# SUPPLY.net
KiCad netlist of a schematic drawn in Altium Designer
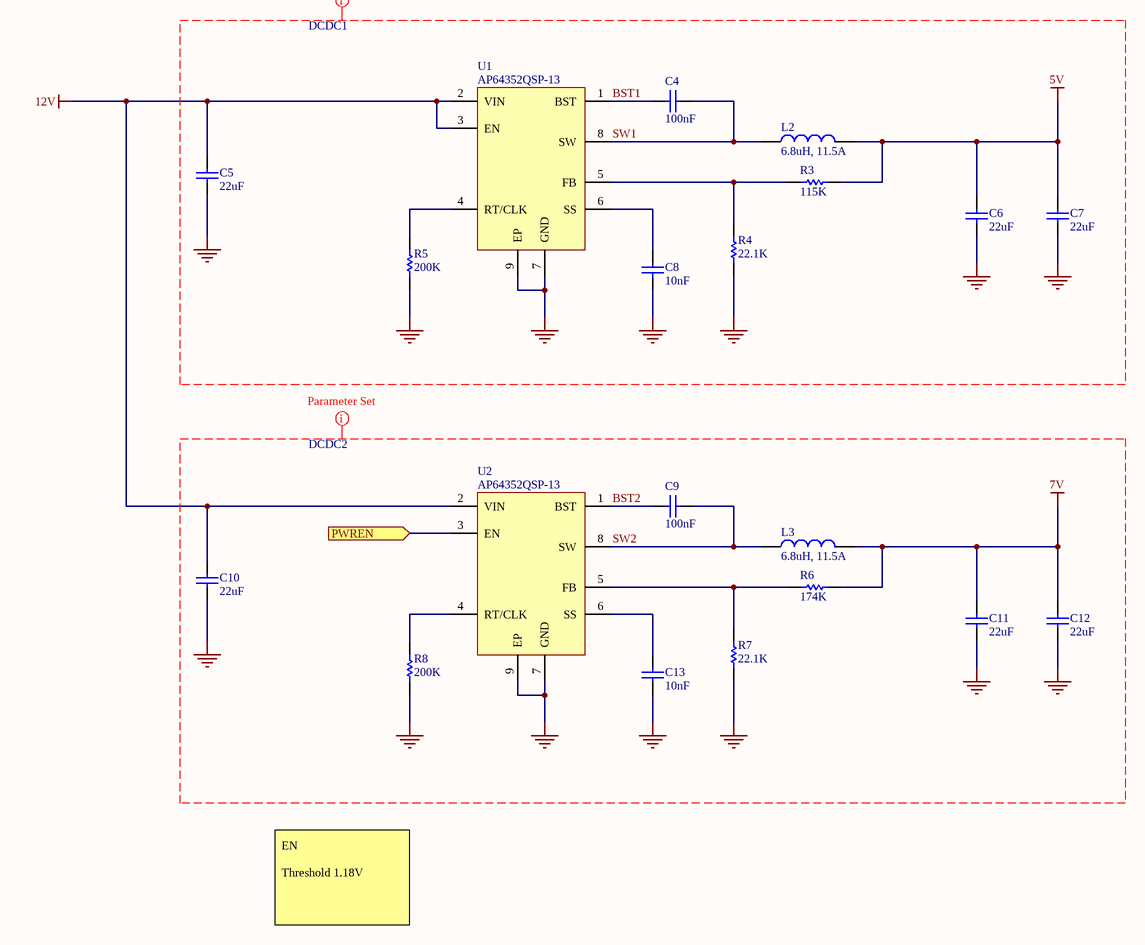
[diagram p0: SUPPLY.SchDoc]

(export (version "E")
  (design (tool "Eeschema 10.0.6"))
  (components
    (comp (ref "C4")
      (value "100nF")
      (footprint "CAP_0603_H090 (_IPC_MD)")
      (description "CAP CER 100NF 50V X7R 0603")
      (fields (field (name "PART NUMBER") "CL10B104KB8NNNC") (field (name "Comment") "100nF 0603"))
      (libsource (lib "MUAB_Altium_Lib") (part "CAP"))
    )
    (comp (ref "C5")
      (value "22uF")
      (footprint "CAP_1210_H090 (_IPC_HD)")
      (description "CAP CER 22UF 25V X7R 1210")
      (fields (field (name "PART NUMBER") "MA1210XR226K250ER") (field (name "Comment") "22uF 1210"))
      (libsource (lib "MUAB_Altium_Lib") (part "CAP"))
    )
    (comp (ref "C6")
      (value "22uF")
      (footprint "CAP_1210_H090 (_IPC_HD)")
      (description "CAP CER 22UF 25V X7R 1210")
      (fields (field (name "PART NUMBER") "MA1210XR226K250ER") (field (name "Comment") "22uF 1210"))
      (libsource (lib "MUAB_Altium_Lib") (part "CAP"))
    )
    (comp (ref "C7")
      (value "22uF")
      (footprint "CAP_1210_H090 (_IPC_HD)")
      (description "CAP CER 22UF 25V X7R 1210")
      (fields (field (name "PART NUMBER") "MA1210XR226K250ER") (field (name "Comment") "22uF 1210"))
      (libsource (lib "MUAB_Altium_Lib") (part "CAP"))
    )
    (comp (ref "C8")
      (value "10nF")
      (footprint "CAP_0603_H090 (_IPC_MD)")
      (description "CAP CER 10NF 50V C0G/NP0 0603")
      (fields (field (name "PART NUMBER") "CGA3E2C0G1H103J080AA") (field (name "Comment") "10nF 0603"))
      (libsource (lib "MUAB_Altium_Lib") (part "CAP"))
    )
    (comp (ref "C9")
      (value "100nF")
      (footprint "CAP_0603_H090 (_IPC_MD)")
      (description "CAP CER 100NF 50V X7R 0603")
      (fields (field (name "PART NUMBER") "CL10B104KB8NNNC") (field (name "Comment") "100nF 0603"))
      (libsource (lib "MUAB_Altium_Lib") (part "CAP"))
    )
    (comp (ref "C10")
      (value "22uF")
      (footprint "CAP_1210_H090 (_IPC_HD)")
      (description "CAP CER 22UF 25V X7R 1210")
      (fields (field (name "PART NUMBER") "MA1210XR226K250ER") (field (name "Comment") "22uF 1210"))
      (libsource (lib "MUAB_Altium_Lib") (part "CAP"))
    )
    (comp (ref "C11")
      (value "22uF")
      (footprint "CAP_1210_H090 (_IPC_HD)")
      (description "CAP CER 22UF 25V X7R 1210")
      (fields (field (name "PART NUMBER") "MA1210XR226K250ER") (field (name "Comment") "22uF 1210"))
      (libsource (lib "MUAB_Altium_Lib") (part "CAP"))
    )
    (comp (ref "C12")
      (value "22uF")
      (footprint "CAP_1210_H090 (_IPC_HD)")
      (description "CAP CER 22UF 25V X7R 1210")
      (fields (field (name "PART NUMBER") "MA1210XR226K250ER") (field (name "Comment") "22uF 1210"))
      (libsource (lib "MUAB_Altium_Lib") (part "CAP"))
    )
    (comp (ref "C13")
      (value "10nF")
      (footprint "CAP_0603_H090 (_IPC_MD)")
      (description "CAP CER 10NF 50V C0G/NP0 0603")
      (fields (field (name "PART NUMBER") "CGA3E2C0G1H103J080AA") (field (name "Comment") "10nF 0603"))
      (libsource (lib "MUAB_Altium_Lib") (part "CAP"))
    )
    (comp (ref "L2")
      (value "6.8uH, 11.5A")
      (footprint "WE-HCC_1090")
      (description "WE-HCC SMT High Current Cube Inductor, size 1090, 6.8uH, 11.5A")
      (fields
        (field (name "MANUFACTURER PART NUMBER") "7443330680")
        (field (name "MANUFACTURER") "Wurth Elektronik")
      )
      (libsource (lib "WE-HCC (rev21a)") (part "7443330680"))
    )
    (comp (ref "L3")
      (value "6.8uH, 11.5A")
      (footprint "WE-HCC_1090")
      (description "WE-HCC SMT High Current Cube Inductor, size 1090, 6.8uH, 11.5A")
      (fields
        (field (name "MANUFACTURER PART NUMBER") "7443330680")
        (field (name "MANUFACTURER") "Wurth Elektronik")
      )
      (libsource (lib "WE-HCC (rev21a)") (part "7443330680"))
    )
    (comp (ref "R3")
      (value "115K")
      (footprint "RES_0603_H050 (_IPC_MD)")
      (description "115K 1% 0,1W 75V 0603")
      (fields (field (name "PART NUMBER") "RES115K1%0603"))
      (libsource (lib "MUAB_Altium_Lib") (part "RES"))
    )
    (comp (ref "R4")
      (value "22.1K")
      (footprint "RES_0603_H050 (_IPC_MD)")
      (description "22.1K 1% 0,1W 75V 0603")
      (fields (field (name "PART NUMBER") "RES22.1K1%0603"))
      (libsource (lib "MUAB_Altium_Lib") (part "RES"))
    )
    (comp (ref "R5")
      (value "200K")
      (footprint "RES_0603_H050 (_IPC_MD)")
      (description "200K 1% 0,1W 75V 0603")
      (fields (field (name "PART NUMBER") "RES200K1%0603"))
      (libsource (lib "MUAB_Altium_Lib") (part "RES"))
    )
    (comp (ref "R6")
      (value "174K")
      (footprint "RES_0603_H050 (_IPC_MD)")
      (description "174K 1% 0,1W 75V 0603")
      (fields (field (name "PART NUMBER") "RES174K1%0603"))
      (libsource (lib "MUAB_Altium_Lib") (part "RES"))
    )
    (comp (ref "R7")
      (value "22.1K")
      (footprint "RES_0603_H050 (_IPC_MD)")
      (description "22.1K 1% 0,1W 75V 0603")
      (fields (field (name "PART NUMBER") "RES22.1K1%0603"))
      (libsource (lib "MUAB_Altium_Lib") (part "RES"))
    )
    (comp (ref "R8")
      (value "200K")
      (footprint "RES_0603_H050 (_IPC_MD)")
      (description "200K 1% 0,1W 75V 0603")
      (fields (field (name "PART NUMBER") "RES200K1%0603"))
      (libsource (lib "MUAB_Altium_Lib") (part "RES"))
    )
    (comp (ref "U1")
      (value "AP64352QSP-13")
      (footprint "SOIC127P600X163-9N")
      (description "DCDC CONV HV BUCK SO-8EP T&R 4K")
      (libsource (lib "MUAB_Altium_Lib") (part "AP64352QSP-13"))
    )
    (comp (ref "U2")
      (value "AP64352QSP-13")
      (footprint "SOIC127P600X163-9N")
      (description "DCDC CONV HV BUCK SO-8EP T&R 4K")
      (libsource (lib "MUAB_Altium_Lib") (part "AP64352QSP-13"))
    )
  )
  (nets
    (net (code "1") (name "/BST1") (class "Default")
      (node (ref "C4") (pin "2") (pinfunction "2_2") (pintype "passive"))
      (node (ref "U1") (pin "1") (pinfunction "BST_1") (pintype "passive"))
    )
    (net (code "2") (name "/BST2") (class "Default")
      (node (ref "C9") (pin "2") (pinfunction "2_2") (pintype "passive"))
      (node (ref "U2") (pin "1") (pinfunction "BST_1") (pintype "passive"))
    )
    (net (code "3") (name "/PWREN") (class "Default")
      (node (ref "U2") (pin "3") (pinfunction "EN_3") (pintype "passive"))
    )
    (net (code "4") (name "/SW1") (class "Default")
      (node (ref "C4") (pin "1") (pinfunction "1_1") (pintype "passive"))
      (node (ref "L2") (pin "1") (pinfunction "1_1") (pintype "passive"))
      (node (ref "U1") (pin "8") (pinfunction "SW_8") (pintype "passive"))
    )
    (net (code "5") (name "/SW2") (class "Default")
      (node (ref "C9") (pin "1") (pinfunction "1_1") (pintype "passive"))
      (node (ref "L3") (pin "1") (pinfunction "1_1") (pintype "passive"))
      (node (ref "U2") (pin "8") (pinfunction "SW_8") (pintype "passive"))
    )
    (net (code "6") (name "5V") (class "Default")
      (node (ref "C6") (pin "2") (pinfunction "2_2") (pintype "passive"))
      (node (ref "C7") (pin "2") (pinfunction "2_2") (pintype "passive"))
      (node (ref "L2") (pin "2") (pinfunction "2_2") (pintype "passive"))
      (node (ref "R3") (pin "2") (pinfunction "2_2") (pintype "passive"))
    )
    (net (code "7") (name "7V") (class "Default")
      (node (ref "C11") (pin "2") (pinfunction "2_2") (pintype "passive"))
      (node (ref "C12") (pin "2") (pinfunction "2_2") (pintype "passive"))
      (node (ref "L3") (pin "2") (pinfunction "2_2") (pintype "passive"))
      (node (ref "R6") (pin "2") (pinfunction "2_2") (pintype "passive"))
    )
    (net (code "8") (name "12V") (class "Default")
      (node (ref "C10") (pin "2") (pinfunction "2_2") (pintype "passive"))
      (node (ref "C5") (pin "2") (pinfunction "2_2") (pintype "passive"))
      (node (ref "U1") (pin "2") (pinfunction "VIN_2") (pintype "passive"))
      (node (ref "U1") (pin "3") (pinfunction "EN_3") (pintype "passive"))
      (node (ref "U2") (pin "2") (pinfunction "VIN_2") (pintype "passive"))
    )
    (net (code "9") (name "GND") (class "Default")
      (node (ref "C10") (pin "1") (pinfunction "1_1") (pintype "passive"))
      (node (ref "C11") (pin "1") (pinfunction "1_1") (pintype "passive"))
      (node (ref "C12") (pin "1") (pinfunction "1_1") (pintype "passive"))
      (node (ref "C13") (pin "1") (pinfunction "1_1") (pintype "passive"))
      (node (ref "C5") (pin "1") (pinfunction "1_1") (pintype "passive"))
      (node (ref "C6") (pin "1") (pinfunction "1_1") (pintype "passive"))
      (node (ref "C7") (pin "1") (pinfunction "1_1") (pintype "passive"))
      (node (ref "C8") (pin "1") (pinfunction "1_1") (pintype "passive"))
      (node (ref "R4") (pin "1") (pinfunction "1_1") (pintype "passive"))
      (node (ref "R5") (pin "1") (pinfunction "1_1") (pintype "passive"))
      (node (ref "R7") (pin "1") (pinfunction "1_1") (pintype "passive"))
      (node (ref "R8") (pin "1") (pinfunction "1_1") (pintype "passive"))
      (node (ref "U1") (pin "7") (pinfunction "GND_7") (pintype "passive"))
      (node (ref "U1") (pin "9") (pinfunction "EP_9") (pintype "passive"))
      (node (ref "U2") (pin "7") (pinfunction "GND_7") (pintype "passive"))
      (node (ref "U2") (pin "9") (pinfunction "EP_9") (pintype "passive"))
    )
    (net (code "10") (name "Net-(U1-FB)") (class "Default")
      (node (ref "R3") (pin "1") (pinfunction "1_1") (pintype "passive"))
      (node (ref "R4") (pin "2") (pinfunction "2_2") (pintype "passive"))
      (node (ref "U1") (pin "5") (pinfunction "FB_5") (pintype "passive"))
    )
    (net (code "11") (name "Net-(U1-RT{slash}CLK)") (class "Default")
      (node (ref "R5") (pin "2") (pinfunction "2_2") (pintype "passive"))
      (node (ref "U1") (pin "4") (pinfunction "RT/CLK_4") (pintype "passive"))
    )
    (net (code "12") (name "Net-(U1-SS)") (class "Default")
      (node (ref "C8") (pin "2") (pinfunction "2_2") (pintype "passive"))
      (node (ref "U1") (pin "6") (pinfunction "SS_6") (pintype "passive"))
    )
    (net (code "13") (name "Net-(U2-FB)") (class "Default")
      (node (ref "R6") (pin "1") (pinfunction "1_1") (pintype "passive"))
      (node (ref "R7") (pin "2") (pinfunction "2_2") (pintype "passive"))
      (node (ref "U2") (pin "5") (pinfunction "FB_5") (pintype "passive"))
    )
    (net (code "14") (name "Net-(U2-RT{slash}CLK)") (class "Default")
      (node (ref "R8") (pin "2") (pinfunction "2_2") (pintype "passive"))
      (node (ref "U2") (pin "4") (pinfunction "RT/CLK_4") (pintype "passive"))
    )
    (net (code "15") (name "Net-(U2-SS)") (class "Default")
      (node (ref "C13") (pin "2") (pinfunction "2_2") (pintype "passive"))
      (node (ref "U2") (pin "6") (pinfunction "SS_6") (pintype "passive"))
    )
  )
)
